# STM32F407ZGT6__2025-05-17.net
KiCad netlist of a schematic drawn in Altium Designer
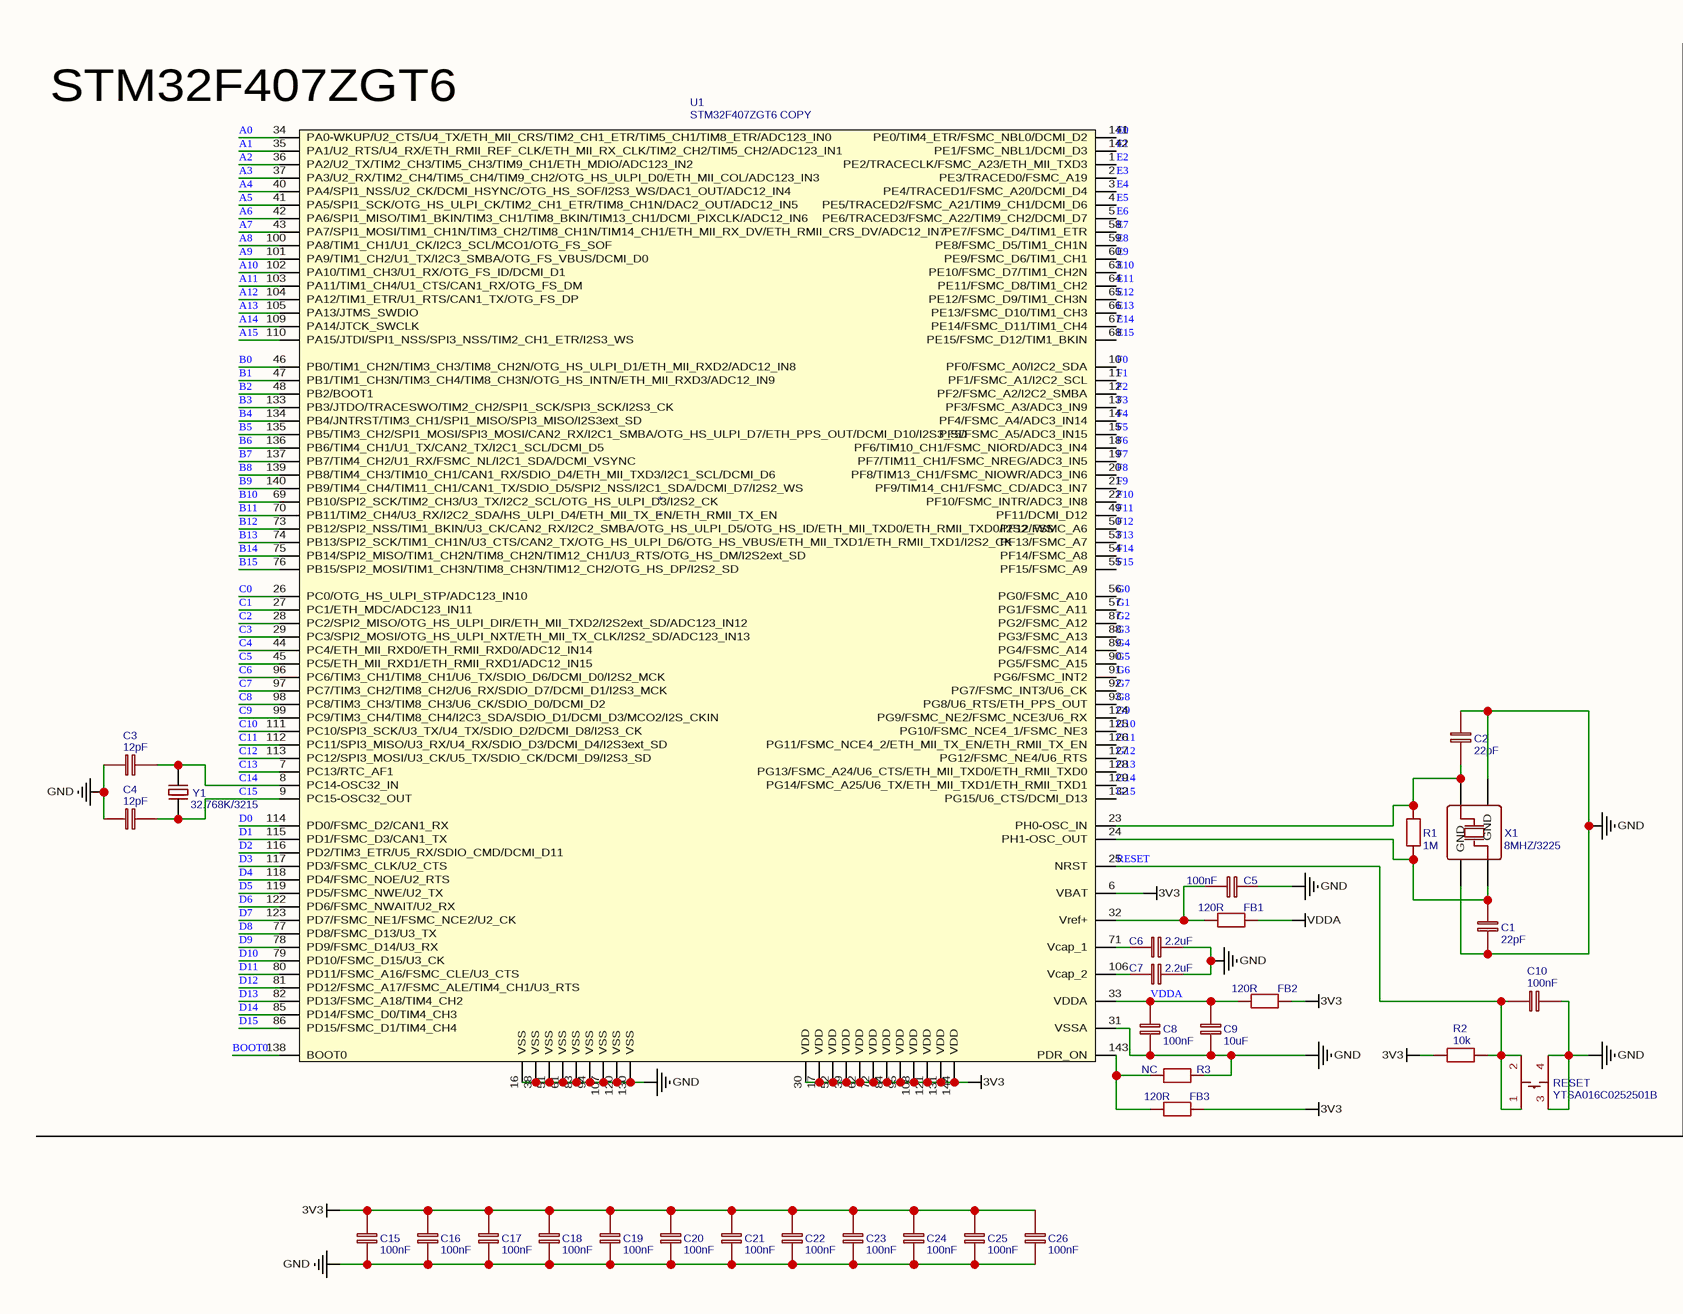
[diagram p0: STM32F407ZGT6最小系统原理图_2025-05-17.schdoc, left]
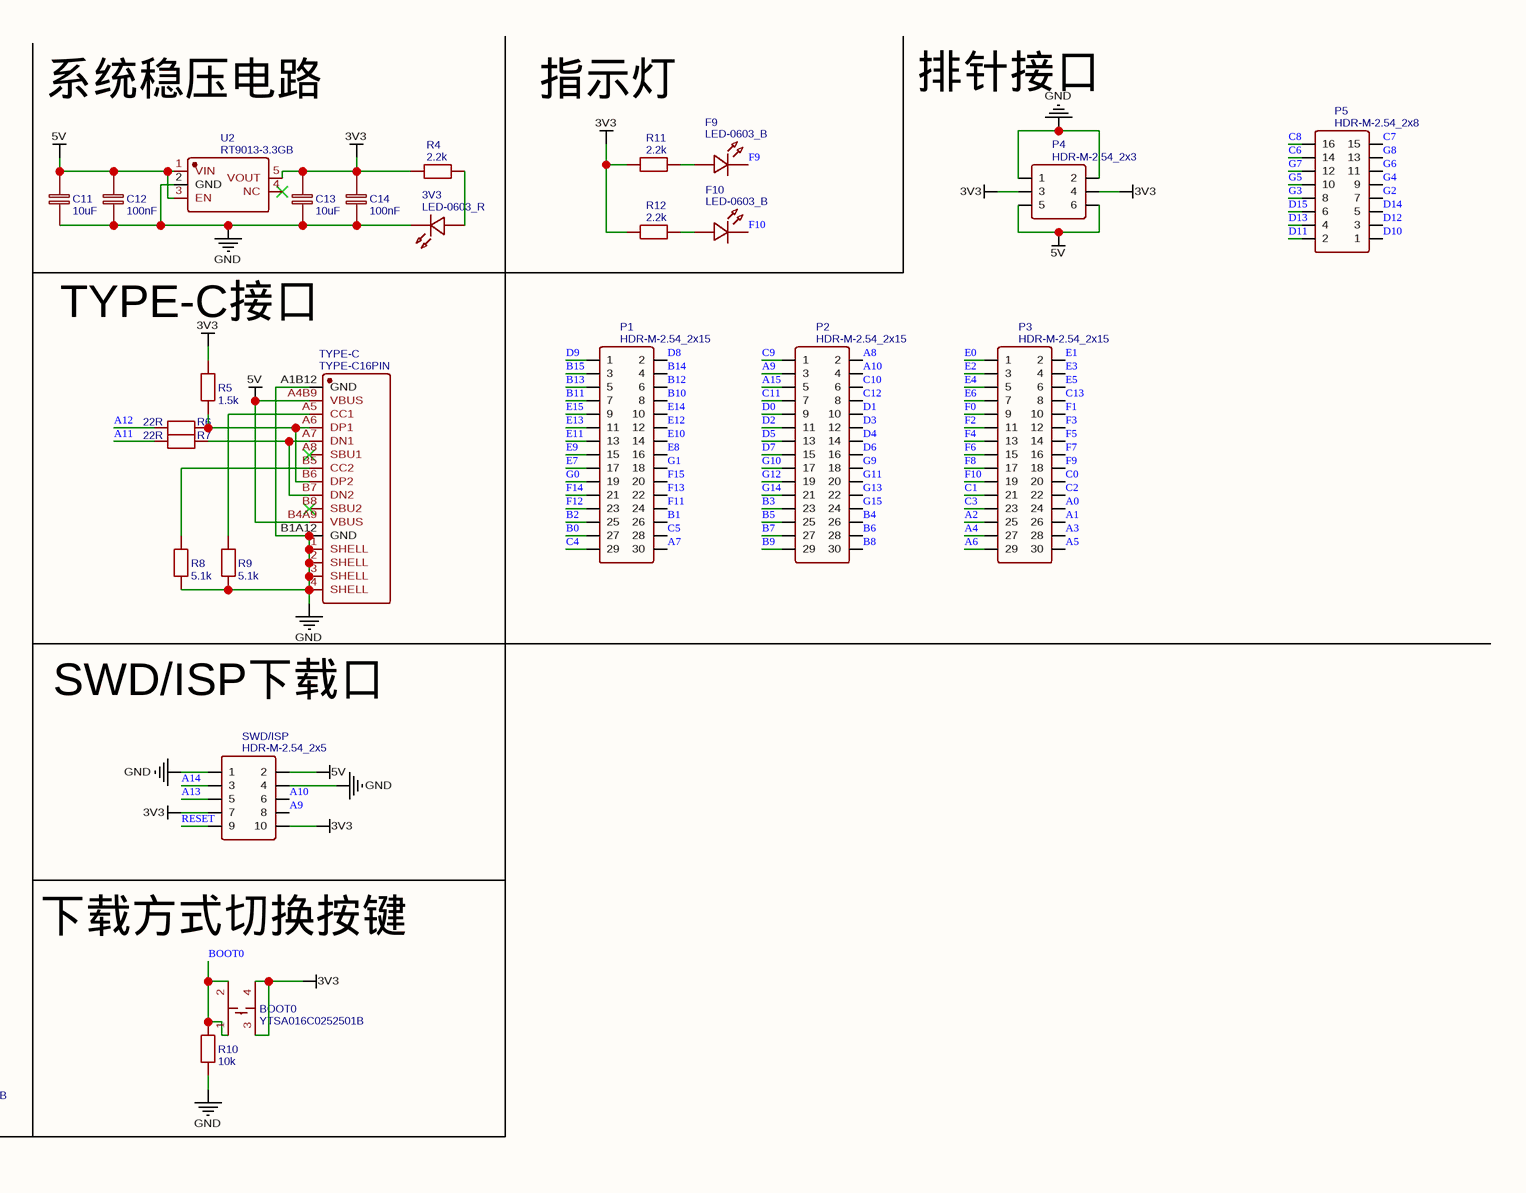
[diagram p1: STM32F407ZGT6最小系统原理图_2025-05-17.schdoc, right]

(export (version "E")
  (design (tool "Eeschema 10.0.6"))
  (components
    (comp (ref "3V3")
      (value "LED-0603_R")
      (fields
        (field (name "MANUFACTURER") "EVERLIGHT(台湾亿光)")
        (field (name "MANUFACTURER PART") "19-217/R6C-AL1M2VY/3T")
      )
      (libsource (lib "altium-import") (part "root_2_LED-0603_R_"))
    )
    (comp (ref "BOOT0")
      (value "YTSA016C0252501B")
      (fields (field (name "MANUFACTURER") "DGBZ"))
      (libsource (lib "altium-import") (part "root_1_YTSA016C0252501B_"))
    )
    (comp (ref "C1") (value "22pF") (libsource (lib "altium-import") (part "root_3_22pF_")))
    (comp (ref "C2") (value "22pF") (libsource (lib "altium-import") (part "root_3_22pF_")))
    (comp (ref "C3") (value "12pF") (libsource (lib "altium-import") (part "root_0_12pF_")))
    (comp (ref "C4") (value "12pF") (libsource (lib "altium-import") (part "root_0_12pF_")))
    (comp (ref "C5") (value "100nF") (libsource (lib "altium-import") (part "root_2_100nF_")))
    (comp (ref "C6") (value "2.2uF") (libsource (lib "altium-import") (part "root_0_2.2uF_")))
    (comp (ref "C7") (value "2.2uF") (libsource (lib "altium-import") (part "root_0_2.2uF_")))
    (comp (ref "C8") (value "100nF") (libsource (lib "altium-import") (part "root_1_100nF_")))
    (comp (ref "C9") (value "10uF") (libsource (lib "altium-import") (part "root_1_10uF_")))
    (comp (ref "C10") (value "100nF") (libsource (lib "altium-import") (part "root_0_100nF_")))
    (comp (ref "C11") (value "10uF") (libsource (lib "altium-import") (part "root_1_10uF_")))
    (comp (ref "C12") (value "100nF") (libsource (lib "altium-import") (part "root_1_100nF_")))
    (comp (ref "C13") (value "10uF") (libsource (lib "altium-import") (part "root_1_10uF_")))
    (comp (ref "C14") (value "100nF") (libsource (lib "altium-import") (part "root_1_100nF_")))
    (comp (ref "C15") (value "100nF") (libsource (lib "altium-import") (part "root_1_100nF_")))
    (comp (ref "C16") (value "100nF") (libsource (lib "altium-import") (part "root_1_100nF_")))
    (comp (ref "C17") (value "100nF") (libsource (lib "altium-import") (part "root_1_100nF_")))
    (comp (ref "C18") (value "100nF") (libsource (lib "altium-import") (part "root_1_100nF_")))
    (comp (ref "C19") (value "100nF") (libsource (lib "altium-import") (part "root_1_100nF_")))
    (comp (ref "C20") (value "100nF") (libsource (lib "altium-import") (part "root_1_100nF_")))
    (comp (ref "C21") (value "100nF") (libsource (lib "altium-import") (part "root_1_100nF_")))
    (comp (ref "C22") (value "100nF") (libsource (lib "altium-import") (part "root_1_100nF_")))
    (comp (ref "C23") (value "100nF") (libsource (lib "altium-import") (part "root_1_100nF_")))
    (comp (ref "C24") (value "100nF") (libsource (lib "altium-import") (part "root_1_100nF_")))
    (comp (ref "C25") (value "100nF") (libsource (lib "altium-import") (part "root_1_100nF_")))
    (comp (ref "C26") (value "100nF") (libsource (lib "altium-import") (part "root_1_100nF_")))
    (comp (ref "F9")
      (value "LED-0603_B")
      (fields
        (field (name "MANUFACTURER") "EVERLIGHT(台湾亿光)")
        (field (name "MANUFACTURER PART") "19-217/BHC-ZL1M2RY/3T")
      )
      (libsource (lib "altium-import") (part "root_0_LED-0603_B_"))
    )
    (comp (ref "F10")
      (value "LED-0603_B")
      (fields
        (field (name "MANUFACTURER") "EVERLIGHT(台湾亿光)")
        (field (name "MANUFACTURER PART") "19-217/BHC-ZL1M2RY/3T")
      )
      (libsource (lib "altium-import") (part "root_0_LED-0603_B_"))
    )
    (comp (ref "FB1") (value "120R") (libsource (lib "altium-import") (part "root_0_120R_")))
    (comp (ref "FB2") (value "120R") (libsource (lib "altium-import") (part "root_0_120R_")))
    (comp (ref "FB3") (value "120R") (libsource (lib "altium-import") (part "root_0_120R_")))
    (comp (ref "P1")
      (value "HDR-M-2.54_2x15")
      (libsource (lib "altium-import") (part "root_0_HDR-M-2.54_2x15_"))
    )
    (comp (ref "P2")
      (value "HDR-M-2.54_2x15")
      (libsource (lib "altium-import") (part "root_0_HDR-M-2.54_2x15_"))
    )
    (comp (ref "P3")
      (value "HDR-M-2.54_2x15")
      (libsource (lib "altium-import") (part "root_0_HDR-M-2.54_2x15_"))
    )
    (comp (ref "P4")
      (value "HDR-M-2.54_2x3")
      (libsource (lib "altium-import") (part "root_0_HDR-M-2.54_2x3_"))
    )
    (comp (ref "P5")
      (value "HDR-M-2.54_2x8")
      (libsource (lib "altium-import") (part "root_2_HDR-M-2.54_2x8_"))
    )
    (comp (ref "R1") (value "1M") (libsource (lib "altium-import") (part "root_1_1M_")))
    (comp (ref "R2") (value "10k") (libsource (lib "altium-import") (part "root_0_10k_")))
    (comp (ref "R3") (value "NC") (libsource (lib "altium-import") (part "root_0_NC_")))
    (comp (ref "R4") (value "2.2k") (libsource (lib "altium-import") (part "root_2_2.2k_")))
    (comp (ref "R5") (value "1.5k") (libsource (lib "altium-import") (part "root_1_1.5k_")))
    (comp (ref "R6") (value "22R") (libsource (lib "altium-import") (part "root_0_22R_")))
    (comp (ref "R7") (value "22R") (libsource (lib "altium-import") (part "root_0_22R_")))
    (comp (ref "R8") (value "5.1k") (libsource (lib "altium-import") (part "root_1_5.1k_")))
    (comp (ref "R9") (value "5.1k") (libsource (lib "altium-import") (part "root_1_5.1k_")))
    (comp (ref "R10") (value "10k") (libsource (lib "altium-import") (part "root_1_10k_")))
    (comp (ref "R11") (value "2.2k") (libsource (lib "altium-import") (part "root_0_2.2k_")))
    (comp (ref "R12") (value "2.2k") (libsource (lib "altium-import") (part "root_0_2.2k_")))
    (comp (ref "RESET")
      (value "YTSA016C0252501B")
      (fields (field (name "MANUFACTURER") "DGBZ"))
      (libsource (lib "altium-import") (part "root_1_YTSA016C0252501B_"))
    )
    (comp (ref "SWD/ISP")
      (value "HDR-M-2.54_2x5")
      (libsource (lib "altium-import") (part "root_0_HDR-M-2.54_2x5_"))
    )
    (comp (ref "TYPE-C")
      (value "TYPE-C16PIN")
      (fields (field (name "MANUFACTURER") "SHOU HAN"))
      (libsource (lib "altium-import") (part "root_0_TYPE-C16PIN_"))
    )
    (comp (ref "U1")
      (value "STM32F407ZGT6 COPY")
      (libsource (lib "altium-import") (part "root_0_STM32F407ZGT6 COPY_"))
    )
    (comp (ref "U2") (value "RT9013-3.3GB") (libsource (lib "altium-import") (part "root_0_RT9013-3.3GB_")))
    (comp (ref "X1")
      (value "8MHZ/3225")
      (fields (field (name "MANUFACTURER PART") "8Mhz/20PF/10PPM/40R内阻/无源晶振3225"))
      (libsource (lib "altium-import") (part "root_1_8MHZ/3225_"))
    )
    (comp (ref "Y1")
      (value "32.768K/3215")
      (fields (field (name "MANUFACTURER PART") "32.768K-OSC3215-2P"))
      (libsource (lib "altium-import") (part "root_1_32.768K/3215_"))
    )
  )
  (nets
    (net (code "1") (name "/A0") (class "Default")
      (node (ref "P3") (pin "24") (pinfunction "24_24") (pintype "passive"))
      (node (ref "U1") (pin "34") (pinfunction "PA0-WKUP/U2_CTS/U4_TX/ETH_MII_CRS/TIM2_CH1_ETR/TIM5_CH1/TIM8_ETR/ADC123_IN0_34") (pintype "passive"))
    )
    (net (code "2") (name "/A1") (class "Default")
      (node (ref "P3") (pin "26") (pinfunction "26_26") (pintype "passive"))
      (node (ref "U1") (pin "35") (pinfunction "PA1/U2_RTS/U4_RX/ETH_RMII_REF_CLK/ETH_MII_RX_CLK/TIM2_CH2/TIM5_CH2/ADC123_IN1_35") (pintype "passive"))
    )
    (net (code "3") (name "/A2") (class "Default")
      (node (ref "P3") (pin "25") (pinfunction "25_25") (pintype "passive"))
      (node (ref "U1") (pin "36") (pinfunction "PA2/U2_TX/TIM2_CH3/TIM5_CH3/TIM9_CH1/ETH_MDIO/ADC123_IN2_36") (pintype "passive"))
    )
    (net (code "4") (name "/A3") (class "Default")
      (node (ref "P3") (pin "28") (pinfunction "28_28") (pintype "passive"))
      (node (ref "U1") (pin "37") (pinfunction "PA3/U2_RX/TIM2_CH4/TIM5_CH4/TIM9_CH2/OTG_HS_ULPI_D0/ETH_MII_COL/ADC123_IN3_37") (pintype "passive"))
    )
    (net (code "5") (name "/A4") (class "Default")
      (node (ref "P3") (pin "27") (pinfunction "27_27") (pintype "passive"))
      (node (ref "U1") (pin "40") (pinfunction "PA4/SPI1_NSS/U2_CK/DCMI_HSYNC/OTG_HS_SOF/I2S3_WS/DAC1_OUT/ADC12_IN4_40") (pintype "passive"))
    )
    (net (code "6") (name "/A5") (class "Default")
      (node (ref "P3") (pin "30") (pinfunction "30_30") (pintype "passive"))
      (node (ref "U1") (pin "41") (pinfunction "PA5/SPI1_SCK/OTG_HS_ULPI_CK/TIM2_CH1_ETR/TIM8_CH1N/DAC2_OUT/ADC12_IN5_41") (pintype "passive"))
    )
    (net (code "7") (name "/A6") (class "Default")
      (node (ref "P3") (pin "29") (pinfunction "29_29") (pintype "passive"))
      (node (ref "U1") (pin "42") (pinfunction "PA6/SPI1_MISO/TIM1_BKIN/TIM3_CH1/TIM8_BKIN/TIM13_CH1/DCMI_PIXCLK/ADC12_IN6_42") (pintype "passive"))
    )
    (net (code "8") (name "/A7") (class "Default")
      (node (ref "P1") (pin "30") (pinfunction "30_30") (pintype "passive"))
      (node (ref "U1") (pin "43") (pinfunction "PA7/SPI1_MOSI/TIM1_CH1N/TIM3_CH2/TIM8_CH1N/TIM14_CH1/ETH_MII_RX_DV/ETH_RMII_CRS_DV/ADC12_IN7_43") (pintype "passive"))
    )
    (net (code "9") (name "/A8") (class "Default")
      (node (ref "P2") (pin "2") (pinfunction "2_2") (pintype "passive"))
      (node (ref "U1") (pin "100") (pinfunction "PA8/TIM1_CH1/U1_CK/I2C3_SCL/MCO1/OTG_FS_SOF_100") (pintype "passive"))
    )
    (net (code "10") (name "/A9") (class "Default")
      (node (ref "P2") (pin "3") (pinfunction "3_3") (pintype "passive"))
      (node (ref "SWD/ISP") (pin "8") (pinfunction "8_8") (pintype "passive"))
      (node (ref "U1") (pin "101") (pinfunction "PA9/TIM1_CH2/U1_TX/I2C3_SMBA/OTG_FS_VBUS/DCMI_D0_101") (pintype "passive"))
    )
    (net (code "11") (name "/A10") (class "Default")
      (node (ref "P2") (pin "4") (pinfunction "4_4") (pintype "passive"))
      (node (ref "SWD/ISP") (pin "6") (pinfunction "6_6") (pintype "passive"))
      (node (ref "U1") (pin "102") (pinfunction "PA10/TIM1_CH3/U1_RX/OTG_FS_ID/DCMI_D1_102") (pintype "passive"))
    )
    (net (code "12") (name "/A11") (class "Default")
      (node (ref "R7") (pin "1") (pinfunction "1_1") (pintype "passive"))
      (node (ref "U1") (pin "103") (pinfunction "PA11/TIM1_CH4/U1_CTS/CAN1_RX/OTG_FS_DM_103") (pintype "passive"))
    )
    (net (code "13") (name "/A12") (class "Default")
      (node (ref "R6") (pin "1") (pinfunction "1_1") (pintype "passive"))
      (node (ref "U1") (pin "104") (pinfunction "PA12/TIM1_ETR/U1_RTS/CAN1_TX/OTG_FS_DP_104") (pintype "passive"))
    )
    (net (code "14") (name "/A13") (class "Default")
      (node (ref "SWD/ISP") (pin "5") (pinfunction "5_5") (pintype "passive"))
      (node (ref "U1") (pin "105") (pinfunction "PA13/JTMS_SWDIO_105") (pintype "passive"))
    )
    (net (code "15") (name "/A14") (class "Default")
      (node (ref "SWD/ISP") (pin "3") (pinfunction "3_3") (pintype "passive"))
      (node (ref "U1") (pin "109") (pinfunction "PA14/JTCK_SWCLK_109") (pintype "passive"))
    )
    (net (code "16") (name "/A15") (class "Default")
      (node (ref "P2") (pin "5") (pinfunction "5_5") (pintype "passive"))
      (node (ref "U1") (pin "110") (pinfunction "PA15/JTDI/SPI1_NSS/SPI3_NSS/TIM2_CH1_ETR/I2S3_WS_110") (pintype "passive"))
    )
    (net (code "17") (name "/B0") (class "Default")
      (node (ref "P1") (pin "27") (pinfunction "27_27") (pintype "passive"))
      (node (ref "U1") (pin "46") (pinfunction "PB0/TIM1_CH2N/TIM3_CH3/TIM8_CH2N/OTG_HS_ULPI_D1/ETH_MII_RXD2/ADC12_IN8_46") (pintype "passive"))
    )
    (net (code "18") (name "/B1") (class "Default")
      (node (ref "P1") (pin "26") (pinfunction "26_26") (pintype "passive"))
      (node (ref "U1") (pin "47") (pinfunction "PB1/TIM1_CH3N/TIM3_CH4/TIM8_CH3N/OTG_HS_INTN/ETH_MII_RXD3/ADC12_IN9_47") (pintype "passive"))
    )
    (net (code "19") (name "/B2") (class "Default")
      (node (ref "P1") (pin "25") (pinfunction "25_25") (pintype "passive"))
      (node (ref "U1") (pin "48") (pinfunction "PB2/BOOT1_48") (pintype "passive"))
    )
    (net (code "20") (name "/B3") (class "Default")
      (node (ref "P2") (pin "23") (pinfunction "23_23") (pintype "passive"))
      (node (ref "U1") (pin "133") (pinfunction "PB3/JTDO/TRACESWO/TIM2_CH2/SPI1_SCK/SPI3_SCK/I2S3_CK_133") (pintype "passive"))
    )
    (net (code "21") (name "/B4") (class "Default")
      (node (ref "P2") (pin "26") (pinfunction "26_26") (pintype "passive"))
      (node (ref "U1") (pin "134") (pinfunction "PB4/JNTRST/TIM3_CH1/SPI1_MISO/SPI3_MISO/I2S3ext_SD_134") (pintype "passive"))
    )
    (net (code "22") (name "/B5") (class "Default")
      (node (ref "P2") (pin "25") (pinfunction "25_25") (pintype "passive"))
      (node (ref "U1") (pin "135") (pinfunction "PB5/TIM3_CH2/SPI1_MOSI/SPI3_MOSI/CAN2_RX/I2C1_SMBA/OTG_HS_ULPI_D7/ETH_PPS_OUT/DCMI_D10/I2S3_SD_135") (pintype "passive"))
    )
    (net (code "23") (name "/B6") (class "Default")
      (node (ref "P2") (pin "28") (pinfunction "28_28") (pintype "passive"))
      (node (ref "U1") (pin "136") (pinfunction "PB6/TIM4_CH1/U1_TX/CAN2_TX/I2C1_SCL/DCMI_D5_136") (pintype "passive"))
    )
    (net (code "24") (name "/B7") (class "Default")
      (node (ref "P2") (pin "27") (pinfunction "27_27") (pintype "passive"))
      (node (ref "U1") (pin "137") (pinfunction "PB7/TIM4_CH2/U1_RX/FSMC_NL/I2C1_SDA/DCMI_VSYNC_137") (pintype "passive"))
    )
    (net (code "25") (name "/B8") (class "Default")
      (node (ref "P2") (pin "30") (pinfunction "30_30") (pintype "passive"))
      (node (ref "U1") (pin "139") (pinfunction "PB8/TIM4_CH3/TIM10_CH1/CAN1_RX/SDIO_D4/ETH_MII_TXD3/I2C1_SCL/DCMI_D6_139") (pintype "passive"))
    )
    (net (code "26") (name "/B9") (class "Default")
      (node (ref "P2") (pin "29") (pinfunction "29_29") (pintype "passive"))
      (node (ref "U1") (pin "140") (pinfunction "PB9/TIM4_CH4/TIM11_CH1/CAN1_TX/SDIO_D5/SPI2_NSS/I2C1_SDA/DCMI_D7/I2S2_WS_140") (pintype "passive"))
    )
    (net (code "27") (name "/B10") (class "Default")
      (node (ref "P1") (pin "8") (pinfunction "8_8") (pintype "passive"))
      (node (ref "U1") (pin "69") (pinfunction "PB10/SPI2_SCK/TIM2_CH3/U3_TX/I2C2_SCL/OTG_HS_ULPI_D3/I2S2_CK_69") (pintype "passive"))
    )
    (net (code "28") (name "/B11") (class "Default")
      (node (ref "P1") (pin "7") (pinfunction "7_7") (pintype "passive"))
      (node (ref "U1") (pin "70") (pinfunction "PB11/TIM2_CH4/U3_RX/I2C2_SDA/HS_ULPI_D4/ETH_MII_TX_EN/ETH_RMII_TX_EN_70") (pintype "passive"))
    )
    (net (code "29") (name "/B12") (class "Default")
      (node (ref "P1") (pin "6") (pinfunction "6_6") (pintype "passive"))
      (node (ref "U1") (pin "73") (pinfunction "PB12/SPI2_NSS/TIM1_BKIN/U3_CK/CAN2_RX/I2C2_SMBA/OTG_HS_ULPI_D5/OTG_HS_ID/ETH_MII_TXD0/ETH_RMII_TXD0/I2S2_WS_73") (pintype "passive"))
    )
    (net (code "30") (name "/B13") (class "Default")
      (node (ref "P1") (pin "5") (pinfunction "5_5") (pintype "passive"))
      (node (ref "U1") (pin "74") (pinfunction "PB13/SPI2_SCK/TIM1_CH1N/U3_CTS/CAN2_TX/OTG_HS_ULPI_D6/OTG_HS_VBUS/ETH_MII_TXD1/ETH_RMII_TXD1/I2S2_CK_74") (pintype "passive"))
    )
    (net (code "31") (name "/B14") (class "Default")
      (node (ref "P1") (pin "4") (pinfunction "4_4") (pintype "passive"))
      (node (ref "U1") (pin "75") (pinfunction "PB14/SPI2_MISO/TIM1_CH2N/TIM8_CH2N/TIM12_CH1/U3_RTS/OTG_HS_DM/I2S2ext_SD_75") (pintype "passive"))
    )
    (net (code "32") (name "/B15") (class "Default")
      (node (ref "P1") (pin "3") (pinfunction "3_3") (pintype "passive"))
      (node (ref "U1") (pin "76") (pinfunction "PB15/SPI2_MOSI/TIM1_CH3N/TIM8_CH3N/TIM12_CH2/OTG_HS_DP/I2S2_SD_76") (pintype "passive"))
    )
    (net (code "33") (name "/BOOT0") (class "Default")
      (node (ref "BOOT0") (pin "1") (pinfunction "1_1") (pintype "passive"))
      (node (ref "BOOT0") (pin "2") (pinfunction "2_2") (pintype "passive"))
      (node (ref "R10") (pin "2") (pinfunction "2_2") (pintype "passive"))
      (node (ref "U1") (pin "138") (pinfunction "BOOT0_138") (pintype "passive"))
    )
    (net (code "34") (name "/C0") (class "Default")
      (node (ref "P3") (pin "20") (pinfunction "20_20") (pintype "passive"))
      (node (ref "U1") (pin "26") (pinfunction "PC0/OTG_HS_ULPI_STP/ADC123_IN10_26") (pintype "passive"))
    )
    (net (code "35") (name "/C1") (class "Default")
      (node (ref "P3") (pin "21") (pinfunction "21_21") (pintype "passive"))
      (node (ref "U1") (pin "27") (pinfunction "PC1/ETH_MDC/ADC123_IN11_27") (pintype "passive"))
    )
    (net (code "36") (name "/C2") (class "Default")
      (node (ref "P3") (pin "22") (pinfunction "22_22") (pintype "passive"))
      (node (ref "U1") (pin "28") (pinfunction "PC2/SPI2_MISO/OTG_HS_ULPI_DIR/ETH_MII_TXD2/I2S2ext_SD/ADC123_IN12_28") (pintype "passive"))
    )
    (net (code "37") (name "/C3") (class "Default")
      (node (ref "P3") (pin "23") (pinfunction "23_23") (pintype "passive"))
      (node (ref "U1") (pin "29") (pinfunction "PC3/SPI2_MOSI/OTG_HS_ULPI_NXT/ETH_MII_TX_CLK/I2S2_SD/ADC123_IN13_29") (pintype "passive"))
    )
    (net (code "38") (name "/C4") (class "Default")
      (node (ref "P1") (pin "29") (pinfunction "29_29") (pintype "passive"))
      (node (ref "U1") (pin "44") (pinfunction "PC4/ETH_MII_RXD0/ETH_RMII_RXD0/ADC12_IN14_44") (pintype "passive"))
    )
    (net (code "39") (name "/C5") (class "Default")
      (node (ref "P1") (pin "28") (pinfunction "28_28") (pintype "passive"))
      (node (ref "U1") (pin "45") (pinfunction "PC5/ETH_MII_RXD1/ETH_RMII_RXD1/ADC12_IN15_45") (pintype "passive"))
    )
    (net (code "40") (name "/C6") (class "Default")
      (node (ref "P5") (pin "14") (pinfunction "14_14") (pintype "passive"))
      (node (ref "U1") (pin "96") (pinfunction "PC6/TIM3_CH1/TIM8_CH1/U6_TX/SDIO_D6/DCMI_D0/I2S2_MCK_96") (pintype "passive"))
    )
    (net (code "41") (name "/C7") (class "Default")
      (node (ref "P5") (pin "15") (pinfunction "15_15") (pintype "passive"))
      (node (ref "U1") (pin "97") (pinfunction "PC7/TIM3_CH2/TIM8_CH2/U6_RX/SDIO_D7/DCMI_D1/I2S3_MCK_97") (pintype "passive"))
    )
    (net (code "42") (name "/C8") (class "Default")
      (node (ref "P5") (pin "16") (pinfunction "16_16") (pintype "passive"))
      (node (ref "U1") (pin "98") (pinfunction "PC8/TIM3_CH3/TIM8_CH3/U6_CK/SDIO_D0/DCMI_D2_98") (pintype "passive"))
    )
    (net (code "43") (name "/C9") (class "Default")
      (node (ref "P2") (pin "1") (pinfunction "1_1") (pintype "passive"))
      (node (ref "U1") (pin "99") (pinfunction "PC9/TIM3_CH4/TIM8_CH4/I2C3_SDA/SDIO_D1/DCMI_D3/MCO2/I2S_CKIN_99") (pintype "passive"))
    )
    (net (code "44") (name "/C10") (class "Default")
      (node (ref "P2") (pin "6") (pinfunction "6_6") (pintype "passive"))
      (node (ref "U1") (pin "111") (pinfunction "PC10/SPI3_SCK/U3_TX/U4_TX/SDIO_D2/DCMI_D8/I2S3_CK_111") (pintype "passive"))
    )
    (net (code "45") (name "/C11") (class "Default")
      (node (ref "P2") (pin "7") (pinfunction "7_7") (pintype "passive"))
      (node (ref "U1") (pin "112") (pinfunction "PC11/SPI3_MISO/U3_RX/U4_RX/SDIO_D3/DCMI_D4/I2S3ext_SD_112") (pintype "passive"))
    )
    (net (code "46") (name "/C12") (class "Default")
      (node (ref "P2") (pin "8") (pinfunction "8_8") (pintype "passive"))
      (node (ref "U1") (pin "113") (pinfunction "PC12/SPI3_MOSI/U3_CK/U5_TX/SDIO_CK/DCMI_D9/I2S3_SD_113") (pintype "passive"))
    )
    (net (code "47") (name "/C13") (class "Default")
      (node (ref "P3") (pin "8") (pinfunction "8_8") (pintype "passive"))
      (node (ref "U1") (pin "7") (pinfunction "PC13/RTC_AF1_7") (pintype "passive"))
    )
    (net (code "48") (name "/C14") (class "Default")
      (node (ref "C3") (pin "2") (pinfunction "2_2") (pintype "passive"))
      (node (ref "U1") (pin "8") (pinfunction "PC14-OSC32_IN_8") (pintype "passive"))
      (node (ref "Y1") (pin "2") (pinfunction "GND_2") (pintype "passive"))
    )
    (net (code "49") (name "/C15") (class "Default")
      (node (ref "C4") (pin "2") (pinfunction "2_2") (pintype "passive"))
      (node (ref "U1") (pin "9") (pinfunction "PC15-OSC32_OUT_9") (pintype "passive"))
      (node (ref "Y1") (pin "1") (pinfunction "1_1") (pintype "passive"))
    )
    (net (code "50") (name "/D0") (class "Default")
      (node (ref "P2") (pin "9") (pinfunction "9_9") (pintype "passive"))
      (node (ref "U1") (pin "114") (pinfunction "PD0/FSMC_D2/CAN1_RX_114") (pintype "passive"))
    )
    (net (code "51") (name "/D1") (class "Default")
      (node (ref "P2") (pin "10") (pinfunction "10_10") (pintype "passive"))
      (node (ref "U1") (pin "115") (pinfunction "PD1/FSMC_D3/CAN1_TX_115") (pintype "passive"))
    )
    (net (code "52") (name "/D2") (class "Default")
      (node (ref "P2") (pin "11") (pinfunction "11_11") (pintype "passive"))
      (node (ref "U1") (pin "116") (pinfunction "PD2/TIM3_ETR/U5_RX/SDIO_CMD/DCMI_D11_116") (pintype "passive"))
    )
    (net (code "53") (name "/D3") (class "Default")
      (node (ref "P2") (pin "12") (pinfunction "12_12") (pintype "passive"))
      (node (ref "U1") (pin "117") (pinfunction "PD3/FSMC_CLK/U2_CTS_117") (pintype "passive"))
    )
    (net (code "54") (name "/D4") (class "Default")
      (node (ref "P2") (pin "14") (pinfunction "14_14") (pintype "passive"))
      (node (ref "U1") (pin "118") (pinfunction "PD4/FSMC_NOE/U2_RTS_118") (pintype "passive"))
    )
    (net (code "55") (name "/D5") (class "Default")
      (node (ref "P2") (pin "13") (pinfunction "13_13") (pintype "passive"))
      (node (ref "U1") (pin "119") (pinfunction "PD5/FSMC_NWE/U2_TX_119") (pintype "passive"))
    )
    (net (code "56") (name "/D6") (class "Default")
      (node (ref "P2") (pin "16") (pinfunction "16_16") (pintype "passive"))
      (node (ref "U1") (pin "122") (pinfunction "PD6/FSMC_NWAIT/U2_RX_122") (pintype "passive"))
    )
    (net (code "57") (name "/D7") (class "Default")
      (node (ref "P2") (pin "15") (pinfunction "15_15") (pintype "passive"))
      (node (ref "U1") (pin "123") (pinfunction "PD7/FSMC_NE1/FSMC_NCE2/U2_CK_123") (pintype "passive"))
    )
    (net (code "58") (name "/D8") (class "Default")
      (node (ref "P1") (pin "2") (pinfunction "2_2") (pintype "passive"))
      (node (ref "U1") (pin "77") (pinfunction "PD8/FSMC_D13/U3_TX_77") (pintype "passive"))
    )
    (net (code "59") (name "/D9") (class "Default")
      (node (ref "P1") (pin "1") (pinfunction "1_1") (pintype "passive"))
      (node (ref "U1") (pin "78") (pinfunction "PD9/FSMC_D14/U3_RX_78") (pintype "passive"))
    )
    (net (code "60") (name "/D10") (class "Default")
      (node (ref "P5") (pin "1") (pinfunction "1_1") (pintype "passive"))
      (node (ref "U1") (pin "79") (pinfunction "PD10/FSMC_D15/U3_CK_79") (pintype "passive"))
    )
    (net (code "61") (name "/D11") (class "Default")
      (node (ref "P5") (pin "2") (pinfunction "2_2") (pintype "passive"))
      (node (ref "U1") (pin "80") (pinfunction "PD11/FSMC_A16/FSMC_CLE/U3_CTS_80") (pintype "passive"))
    )
    (net (code "62") (name "/D12") (class "Default")
      (node (ref "P5") (pin "3") (pinfunction "3_3") (pintype "passive"))
      (node (ref "U1") (pin "81") (pinfunction "PD12/FSMC_A17/FSMC_ALE/TIM4_CH1/U3_RTS_81") (pintype "passive"))
    )
    (net (code "63") (name "/D13") (class "Default")
      (node (ref "P5") (pin "4") (pinfunction "4_4") (pintype "passive"))
      (node (ref "U1") (pin "82") (pinfunction "PD13/FSMC_A18/TIM4_CH2_82") (pintype "passive"))
    )
    (net (code "64") (name "/D14") (class "Default")
      (node (ref "P5") (pin "5") (pinfunction "5_5") (pintype "passive"))
      (node (ref "U1") (pin "85") (pinfunction "PD14/FSMC_D0/TIM4_CH3_85") (pintype "passive"))
    )
    (net (code "65") (name "/D15") (class "Default")
      (node (ref "P5") (pin "6") (pinfunction "6_6") (pintype "passive"))
      (node (ref "U1") (pin "86") (pinfunction "PD15/FSMC_D1/TIM4_CH4_86") (pintype "passive"))
    )
    (net (code "66") (name "/E0") (class "Default")
      (node (ref "P3") (pin "1") (pinfunction "1_1") (pintype "passive"))
      (node (ref "U1") (pin "141") (pinfunction "PE0/TIM4_ETR/FSMC_NBL0/DCMI_D2_141") (pintype "passive"))
    )
    (net (code "67") (name "/E1") (class "Default")
      (node (ref "P3") (pin "2") (pinfunction "2_2") (pintype "passive"))
      (node (ref "U1") (pin "142") (pinfunction "PE1/FSMC_NBL1/DCMI_D3_142") (pintype "passive"))
    )
    (net (code "68") (name "/E2") (class "Default")
      (node (ref "P3") (pin "3") (pinfunction "3_3") (pintype "passive"))
      (node (ref "U1") (pin "1") (pinfunction "PE2/TRACECLK/FSMC_A23/ETH_MII_TXD3_1") (pintype "passive"))
    )
    (net (code "69") (name "/E3") (class "Default")
      (node (ref "P3") (pin "4") (pinfunction "4_4") (pintype "passive"))
      (node (ref "U1") (pin "2") (pinfunction "PE3/TRACED0/FSMC_A19_2") (pintype "passive"))
    )
    (net (code "70") (name "/E4") (class "Default")
      (node (ref "P3") (pin "5") (pinfunction "5_5") (pintype "passive"))
      (node (ref "U1") (pin "3") (pinfunction "PE4/TRACED1/FSMC_A20/DCMI_D4_3") (pintype "passive"))
    )
    (net (code "71") (name "/E5") (class "Default")
      (node (ref "P3") (pin "6") (pinfunction "6_6") (pintype "passive"))
      (node (ref "U1") (pin "4") (pinfunction "PE5/TRACED2/FSMC_A21/TIM9_CH1/DCMI_D6_4") (pintype "passive"))
    )
    (net (code "72") (name "/E6") (class "Default")
      (node (ref "P3") (pin "7") (pinfunction "7_7") (pintype "passive"))
      (node (ref "U1") (pin "5") (pinfunction "PE6/TRACED3/FSMC_A22/TIM9_CH2/DCMI_D7_5") (pintype "passive"))
    )
    (net (code "73") (name "/E7") (class "Default")
      (node (ref "P1") (pin "17") (pinfunction "17_17") (pintype "passive"))
      (node (ref "U1") (pin "58") (pinfunction "PE7/FSMC_D4/TIM1_ETR_58") (pintype "passive"))
    )
    (net (code "74") (name "/E8") (class "Default")
      (node (ref "P1") (pin "16") (pinfunction "16_16") (pintype "passive"))
      (node (ref "U1") (pin "59") (pinfunction "PE8/FSMC_D5/TIM1_CH1N_59") (pintype "passive"))
    )
    (net (code "75") (name "/E9") (class "Default")
      (node (ref "P1") (pin "15") (pinfunction "15_15") (pintype "passive"))
      (node (ref "U1") (pin "60") (pinfunction "PE9/FSMC_D6/TIM1_CH1_60") (pintype "passive"))
    )
    (net (code "76") (name "/E10") (class "Default")
      (node (ref "P1") (pin "14") (pinfunction "14_14") (pintype "passive"))
      (node (ref "U1") (pin "63") (pinfunction "PE10/FSMC_D7/TIM1_CH2N_63") (pintype "passive"))
    )
    (net (code "77") (name "/E11") (class "Default")
      (node (ref "P1") (pin "13") (pinfunction "13_13") (pintype "passive"))
      (node (ref "U1") (pin "64") (pinfunction "PE11/FSMC_D8/TIM1_CH2_64") (pintype "passive"))
    )
    (net (code "78") (name "/E12") (class "Default")
      (node (ref "P1") (pin "12") (pinfunction "12_12") (pintype "passive"))
      (node (ref "U1") (pin "65") (pinfunction "PE12/FSMC_D9/TIM1_CH3N_65") (pintype "passive"))
    )
    (net (code "79") (name "/E13") (class "Default")
      (node (ref "P1") (pin "11") (pinfunction "11_11") (pintype "passive"))
      (node (ref "U1") (pin "66") (pinfunction "PE13/FSMC_D10/TIM1_CH3_66") (pintype "passive"))
    )
    (net (code "80") (name "/E14") (class "Default")
      (node (ref "P1") (pin "10") (pinfunction "10_10") (pintype "passive"))
      (node (ref "U1") (pin "67") (pinfunction "PE14/FSMC_D11/TIM1_CH4_67") (pintype "passive"))
    )
    (net (code "81") (name "/E15") (class "Default")
      (node (ref "P1") (pin "9") (pinfunction "9_9") (pintype "passive"))
      (node (ref "U1") (pin "68") (pinfunction "PE15/FSMC_D12/TIM1_BKIN_68") (pintype "passive"))
    )
    (net (code "82") (name "/F0") (class "Default")
      (node (ref "P3") (pin "9") (pinfunction "9_9") (pintype "passive"))
      (node (ref "U1") (pin "10") (pinfunction "PF0/FSMC_A0/I2C2_SDA_10") (pintype "passive"))
    )
    (net (code "83") (name "/F1") (class "Default")
      (node (ref "P3") (pin "10") (pinfunction "10_10") (pintype "passive"))
      (node (ref "U1") (pin "11") (pinfunction "PF1/FSMC_A1/I2C2_SCL_11") (pintype "passive"))
    )
    (net (code "84") (name "/F2") (class "Default")
      (node (ref "P3") (pin "11") (pinfunction "11_11") (pintype "passive"))
      (node (ref "U1") (pin "12") (pinfunction "PF2/FSMC_A2/I2C2_SMBA_12") (pintype "passive"))
    )
    (net (code "85") (name "/F3") (class "Default")
      (node (ref "P3") (pin "12") (pinfunction "12_12") (pintype "passive"))
      (node (ref "U1") (pin "13") (pinfunction "PF3/FSMC_A3/ADC3_IN9_13") (pintype "passive"))
    )
    (net (code "86") (name "/F4") (class "Default")
      (node (ref "P3") (pin "13") (pinfunction "13_13") (pintype "passive"))
      (node (ref "U1") (pin "14") (pinfunction "PF4/FSMC_A4/ADC3_IN14_14") (pintype "passive"))
    )
    (net (code "87") (name "/F5") (class "Default")
      (node (ref "P3") (pin "14") (pinfunction "14_14") (pintype "passive"))
      (node (ref "U1") (pin "15") (pinfunction "PF5/FSMC_A5/ADC3_IN15_15") (pintype "passive"))
    )
    (net (code "88") (name "/F6") (class "Default")
      (node (ref "P3") (pin "15") (pinfunction "15_15") (pintype "passive"))
      (node (ref "U1") (pin "18") (pinfunction "PF6/TIM10_CH1/FSMC_NIORD/ADC3_IN4_18") (pintype "passive"))
    )
    (net (code "89") (name "/F7") (class "Default")
      (node (ref "P3") (pin "16") (pinfunction "16_16") (pintype "passive"))
      (node (ref "U1") (pin "19") (pinfunction "PF7/TIM11_CH1/FSMC_NREG/ADC3_IN5_19") (pintype "passive"))
    )
    (net (code "90") (name "/F8") (class "Default")
      (node (ref "P3") (pin "17") (pinfunction "17_17") (pintype "passive"))
      (node (ref "U1") (pin "20") (pinfunction "PF8/TIM13_CH1/FSMC_NIOWR/ADC3_IN6_20") (pintype "passive"))
    )
    (net (code "91") (name "/F9") (class "Default")
      (node (ref "F9") (pin "2") (pinfunction "2_2") (pintype "passive"))
      (node (ref "P3") (pin "18") (pinfunction "18_18") (pintype "passive"))
      (node (ref "U1") (pin "21") (pinfunction "PF9/TIM14_CH1/FSMC_CD/ADC3_IN7_21") (pintype "passive"))
    )
    (net (code "92") (name "/F10") (class "Default")
      (node (ref "F10") (pin "2") (pinfunction "2_2") (pintype "passive"))
      (node (ref "P3") (pin "19") (pinfunction "19_19") (pintype "passive"))
      (node (ref "U1") (pin "22") (pinfunction "PF10/FSMC_INTR/ADC3_IN8_22") (pintype "passive"))
    )
    (net (code "93") (name "/F11") (class "Default")
      (node (ref "P1") (pin "24") (pinfunction "24_24") (pintype "passive"))
      (node (ref "U1") (pin "49") (pinfunction "PF11/DCMI_D12_49") (pintype "passive"))
    )
    (net (code "94") (name "/F12") (class "Default")
      (node (ref "P1") (pin "23") (pinfunction "23_23") (pintype "passive"))
      (node (ref "U1") (pin "50") (pinfunction "PF12/FSMC_A6_50") (pintype "passive"))
    )
    (net (code "95") (name "/F13") (class "Default")
      (node (ref "P1") (pin "22") (pinfunction "22_22") (pintype "passive"))
      (node (ref "U1") (pin "53") (pinfunction "PF13/FSMC_A7_53") (pintype "passive"))
    )
    (net (code "96") (name "/F14") (class "Default")
      (node (ref "P1") (pin "21") (pinfunction "21_21") (pintype "passive"))
      (node (ref "U1") (pin "54") (pinfunction "PF14/FSMC_A8_54") (pintype "passive"))
    )
    (net (code "97") (name "/F15") (class "Default")
      (node (ref "P1") (pin "20") (pinfunction "20_20") (pintype "passive"))
      (node (ref "U1") (pin "55") (pinfunction "PF15/FSMC_A9_55") (pintype "passive"))
    )
    (net (code "98") (name "/G0") (class "Default")
      (node (ref "P1") (pin "19") (pinfunction "19_19") (pintype "passive"))
      (node (ref "U1") (pin "56") (pinfunction "PG0/FSMC_A10_56") (pintype "passive"))
    )
    (net (code "99") (name "/G1") (class "Default")
      (node (ref "P1") (pin "18") (pinfunction "18_18") (pintype "passive"))
      (node (ref "U1") (pin "57") (pinfunction "PG1/FSMC_A11_57") (pintype "passive"))
    )
    (net (code "100") (name "/G2") (class "Default")
      (node (ref "P5") (pin "7") (pinfunction "7_7") (pintype "passive"))
      (node (ref "U1") (pin "87") (pinfunction "PG2/FSMC_A12_87") (pintype "passive"))
    )
    (net (code "101") (name "/G3") (class "Default")
      (node (ref "P5") (pin "8") (pinfunction "8_8") (pintype "passive"))
      (node (ref "U1") (pin "88") (pinfunction "PG3/FSMC_A13_88") (pintype "passive"))
    )
    (net (code "102") (name "/G4") (class "Default")
      (node (ref "P5") (pin "9") (pinfunction "9_9") (pintype "passive"))
      (node (ref "U1") (pin "89") (pinfunction "PG4/FSMC_A14_89") (pintype "passive"))
    )
    (net (code "103") (name "/G5") (class "Default")
      (node (ref "P5") (pin "10") (pinfunction "10_10") (pintype "passive"))
      (node (ref "U1") (pin "90") (pinfunction "PG5/FSMC_A15_90") (pintype "passive"))
    )
    (net (code "104") (name "/G6") (class "Default")
      (node (ref "P5") (pin "11") (pinfunction "11_11") (pintype "passive"))
      (node (ref "U1") (pin "91") (pinfunction "PG6/FSMC_INT2_91") (pintype "passive"))
    )
    (net (code "105") (name "/G7") (class "Default")
      (node (ref "P5") (pin "12") (pinfunction "12_12") (pintype "passive"))
      (node (ref "U1") (pin "92") (pinfunction "PG7/FSMC_INT3/U6_CK_92") (pintype "passive"))
    )
    (net (code "106") (name "/G8") (class "Default")
      (node (ref "P5") (pin "13") (pinfunction "13_13") (pintype "passive"))
      (node (ref "U1") (pin "93") (pinfunction "PG8/U6_RTS/ETH_PPS_OUT_93") (pintype "passive"))
    )
    (net (code "107") (name "/G9") (class "Default")
      (node (ref "P2") (pin "18") (pinfunction "18_18") (pintype "passive"))
      (node (ref "U1") (pin "124") (pinfunction "PG9/FSMC_NE2/FSMC_NCE3/U6_RX_124") (pintype "passive"))
    )
    (net (code "108") (name "/G10") (class "Default")
      (node (ref "P2") (pin "17") (pinfunction "17_17") (pintype "passive"))
      (node (ref "U1") (pin "125") (pinfunction "PG10/FSMC_NCE4_1/FSMC_NE3_125") (pintype "passive"))
    )
    (net (code "109") (name "/G11") (class "Default")
      (node (ref "P2") (pin "20") (pinfunction "20_20") (pintype "passive"))
      (node (ref "U1") (pin "126") (pinfunction "PG11/FSMC_NCE4_2/ETH_MII_TX_EN/ETH_RMII_TX_EN_126") (pintype "passive"))
    )
    (net (code "110") (name "/G12") (class "Default")
      (node (ref "P2") (pin "19") (pinfunction "19_19") (pintype "passive"))
      (node (ref "U1") (pin "127") (pinfunction "PG12/FSMC_NE4/U6_RTS_127") (pintype "passive"))
    )
    (net (code "111") (name "/G13") (class "Default")
      (node (ref "P2") (pin "22") (pinfunction "22_22") (pintype "passive"))
      (node (ref "U1") (pin "128") (pinfunction "PG13/FSMC_A24/U6_CTS/ETH_MII_TXD0/ETH_RMII_TXD0_128") (pintype "passive"))
    )
    (net (code "112") (name "/G14") (class "Default")
      (node (ref "P2") (pin "21") (pinfunction "21_21") (pintype "passive"))
      (node (ref "U1") (pin "129") (pinfunction "PG14/FSMC_A25/U6_TX/ETH_MII_TXD1/ETH_RMII_TXD1_129") (pintype "passive"))
    )
    (net (code "113") (name "/G15") (class "Default")
      (node (ref "P2") (pin "24") (pinfunction "24_24") (pintype "passive"))
      (node (ref "U1") (pin "132") (pinfunction "PG15/U6_CTS/DCMI_D13_132") (pintype "passive"))
    )
    (net (code "114") (name "/RESET") (class "Default")
      (node (ref "C10") (pin "1") (pinfunction "1_1") (pintype "passive"))
      (node (ref "R2") (pin "2") (pinfunction "2_2") (pintype "passive"))
      (node (ref "RESET") (pin "1") (pinfunction "1_1") (pintype "passive"))
      (node (ref "RESET") (pin "2") (pinfunction "2_2") (pintype "passive"))
      (node (ref "SWD/ISP") (pin "9") (pinfunction "9_9") (pintype "passive"))
      (node (ref "U1") (pin "25") (pinfunction "NRST_25") (pintype "passive"))
    )
    (net (code "115") (name "3V3") (class "Default")
      (node (ref "BOOT0") (pin "3") (pinfunction "3_3") (pintype "passive"))
      (node (ref "BOOT0") (pin "4") (pinfunction "4_4") (pintype "passive"))
      (node (ref "C13") (pin "2") (pinfunction "2_2") (pintype "passive"))
      (node (ref "C14") (pin "2") (pinfunction "2_2") (pintype "passive"))
      (node (ref "C15") (pin "2") (pinfunction "2_2") (pintype "passive"))
      (node (ref "C16") (pin "2") (pinfunction "2_2") (pintype "passive"))
      (node (ref "C17") (pin "2") (pinfunction "2_2") (pintype "passive"))
      (node (ref "C18") (pin "2") (pinfunction "2_2") (pintype "passive"))
      (node (ref "C19") (pin "2") (pinfunction "2_2") (pintype "passive"))
      (node (ref "C20") (pin "2") (pinfunction "2_2") (pintype "passive"))
      (node (ref "C21") (pin "2") (pinfunction "2_2") (pintype "passive"))
      (node (ref "C22") (pin "2") (pinfunction "2_2") (pintype "passive"))
      (node (ref "C23") (pin "2") (pinfunction "2_2") (pintype "passive"))
      (node (ref "C24") (pin "2") (pinfunction "2_2") (pintype "passive"))
      (node (ref "C25") (pin "2") (pinfunction "2_2") (pintype "passive"))
      (node (ref "C26") (pin "2") (pinfunction "2_2") (pintype "passive"))
      (node (ref "FB2") (pin "2") (pinfunction "2_2") (pintype "passive"))
      (node (ref "FB3") (pin "2") (pinfunction "2_2") (pintype "passive"))
      (node (ref "P4") (pin "3") (pinfunction "3_3") (pintype "passive"))
      (node (ref "P4") (pin "4") (pinfunction "4_4") (pintype "passive"))
      (node (ref "R11") (pin "1") (pinfunction "1_1") (pintype "passive"))
      (node (ref "R12") (pin "1") (pinfunction "1_1") (pintype "passive"))
      (node (ref "R2") (pin "1") (pinfunction "1_1") (pintype "passive"))
      (node (ref "R4") (pin "2") (pinfunction "2_2") (pintype "passive"))
      (node (ref "R5") (pin "2") (pinfunction "2_2") (pintype "passive"))
      (node (ref "SWD/ISP") (pin "10") (pinfunction "10_10") (pintype "passive"))
      (node (ref "SWD/ISP") (pin "7") (pinfunction "7_7") (pintype "passive"))
      (node (ref "U1") (pin "108") (pinfunction "VDD_108") (pintype "passive"))
      (node (ref "U1") (pin "121") (pinfunction "VDD_121") (pintype "passive"))
      (node (ref "U1") (pin "131") (pinfunction "VDD_131") (pintype "passive"))
      (node (ref "U1") (pin "144") (pinfunction "VDD_144") (pintype "passive"))
      (node (ref "U1") (pin "17") (pinfunction "VDD_17") (pintype "passive"))
      (node (ref "U1") (pin "30") (pinfunction "VDD_30") (pintype "passive"))
      (node (ref "U1") (pin "39") (pinfunction "VDD_39") (pintype "passive"))
      (node (ref "U1") (pin "52") (pinfunction "VDD_52") (pintype "passive"))
      (node (ref "U1") (pin "6") (pinfunction "VBAT_6") (pintype "passive"))
      (node (ref "U1") (pin "62") (pinfunction "VDD_62") (pintype "passive"))
      (node (ref "U1") (pin "72") (pinfunction "VDD_72") (pintype "passive"))
      (node (ref "U1") (pin "84") (pinfunction "VDD_84") (pintype "passive"))
      (node (ref "U1") (pin "95") (pinfunction "VDD_95") (pintype "passive"))
      (node (ref "U2") (pin "5") (pinfunction "VOUT_5") (pintype "passive"))
    )
    (net (code "116") (name "5V") (class "Default")
      (node (ref "C11") (pin "2") (pinfunction "2_2") (pintype "passive"))
      (node (ref "C12") (pin "2") (pinfunction "2_2") (pintype "passive"))
      (node (ref "P4") (pin "5") (pinfunction "5_5") (pintype "passive"))
      (node (ref "P4") (pin "6") (pinfunction "6_6") (pintype "passive"))
      (node (ref "SWD/ISP") (pin "2") (pinfunction "2_2") (pintype "passive"))
      (node (ref "TYPE-C") (pin "A4B9") (pinfunction "VBUS_A4B9") (pintype "passive"))
      (node (ref "TYPE-C") (pin "B4A9") (pinfunction "VBUS_B4A9") (pintype "passive"))
      (node (ref "U2") (pin "1") (pinfunction "VIN_1") (pintype "passive"))
      (node (ref "U2") (pin "3") (pinfunction "EN_3") (pintype "passive"))
    )
    (net (code "117") (name "GND") (class "Default")
      (node (ref "3V3") (pin "2") (pinfunction "2_2") (pintype "passive"))
      (node (ref "C1") (pin "2") (pinfunction "2_2") (pintype "passive"))
      (node (ref "C10") (pin "2") (pinfunction "2_2") (pintype "passive"))
      (node (ref "C11") (pin "1") (pinfunction "1_1") (pintype "passive"))
      (node (ref "C12") (pin "1") (pinfunction "1_1") (pintype "passive"))
      (node (ref "C13") (pin "1") (pinfunction "1_1") (pintype "passive"))
      (node (ref "C14") (pin "1") (pinfunction "1_1") (pintype "passive"))
      (node (ref "C15") (pin "1") (pinfunction "1_1") (pintype "passive"))
      (node (ref "C16") (pin "1") (pinfunction "1_1") (pintype "passive"))
      (node (ref "C17") (pin "1") (pinfunction "1_1") (pintype "passive"))
      (node (ref "C18") (pin "1") (pinfunction "1_1") (pintype "passive"))
      (node (ref "C19") (pin "1") (pinfunction "1_1") (pintype "passive"))
      (node (ref "C2") (pin "1") (pinfunction "1_1") (pintype "passive"))
      (node (ref "C20") (pin "1") (pinfunction "1_1") (pintype "passive"))
      (node (ref "C21") (pin "1") (pinfunction "1_1") (pintype "passive"))
      (node (ref "C22") (pin "1") (pinfunction "1_1") (pintype "passive"))
      (node (ref "C23") (pin "1") (pinfunction "1_1") (pintype "passive"))
      (node (ref "C24") (pin "1") (pinfunction "1_1") (pintype "passive"))
      (node (ref "C25") (pin "1") (pinfunction "1_1") (pintype "passive"))
      (node (ref "C26") (pin "1") (pinfunction "1_1") (pintype "passive"))
      (node (ref "C3") (pin "1") (pinfunction "1_1") (pintype "passive"))
      (node (ref "C4") (pin "1") (pinfunction "1_1") (pintype "passive"))
      (node (ref "C5") (pin "1") (pinfunction "1_1") (pintype "passive"))
      (node (ref "C6") (pin "2") (pinfunction "2_2") (pintype "passive"))
      (node (ref "C7") (pin "2") (pinfunction "2_2") (pintype "passive"))
      (node (ref "C8") (pin "1") (pinfunction "1_1") (pintype "passive"))
      (node (ref "C9") (pin "1") (pinfunction "1_1") (pintype "passive"))
      (node (ref "P4") (pin "1") (pinfunction "1_1") (pintype "passive"))
      (node (ref "P4") (pin "2") (pinfunction "2_2") (pintype "passive"))
      (node (ref "R10") (pin "1") (pinfunction "1_1") (pintype "passive"))
      (node (ref "R3") (pin "2") (pinfunction "2_2") (pintype "passive"))
      (node (ref "R8") (pin "1") (pinfunction "1_1") (pintype "passive"))
      (node (ref "R9") (pin "1") (pinfunction "1_1") (pintype "passive"))
      (node (ref "RESET") (pin "3") (pinfunction "3_3") (pintype "passive"))
      (node (ref "RESET") (pin "4") (pinfunction "4_4") (pintype "passive"))
      (node (ref "SWD/ISP") (pin "1") (pinfunction "1_1") (pintype "passive"))
      (node (ref "SWD/ISP") (pin "4") (pinfunction "4_4") (pintype "passive"))
      (node (ref "TYPE-C") (pin "1") (pinfunction "SHELL_1") (pintype "passive"))
      (node (ref "TYPE-C") (pin "2") (pinfunction "SHELL_2") (pintype "passive"))
      (node (ref "TYPE-C") (pin "3") (pinfunction "SHELL_3") (pintype "passive"))
      (node (ref "TYPE-C") (pin "4") (pinfunction "SHELL_4") (pintype "passive"))
      (node (ref "TYPE-C") (pin "A1B12") (pinfunction "GND_A1B12") (pintype "passive"))
      (node (ref "TYPE-C") (pin "B1A12") (pinfunction "GND_B1A12") (pintype "passive"))
      (node (ref "U1") (pin "107") (pinfunction "VSS_107") (pintype "passive"))
      (node (ref "U1") (pin "120") (pinfunction "VSS_120") (pintype "passive"))
      (node (ref "U1") (pin "130") (pinfunction "VSS_130") (pintype "passive"))
      (node (ref "U1") (pin "16") (pinfunction "VSS_16") (pintype "passive"))
      (node (ref "U1") (pin "31") (pinfunction "VSSA_31") (pintype "passive"))
      (node (ref "U1") (pin "38") (pinfunction "VSS_38") (pintype "passive"))
      (node (ref "U1") (pin "51") (pinfunction "VSS_51") (pintype "passive"))
      (node (ref "U1") (pin "61") (pinfunction "VSS_61") (pintype "passive"))
      (node (ref "U1") (pin "83") (pinfunction "VSS_83") (pintype "passive"))
      (node (ref "U1") (pin "94") (pinfunction "VSS_94") (pintype "passive"))
      (node (ref "U2") (pin "2") (pinfunction "GND_2") (pintype "passive"))
      (node (ref "X1") (pin "2") (pinfunction "GND_2") (pintype "passive"))
      (node (ref "X1") (pin "4") (pinfunction "GND_4") (pintype "passive"))
    )
    (net (code "118") (name "Net-(3V3-Pad1)") (class "Default")
      (node (ref "3V3") (pin "1") (pinfunction "1_1") (pintype "passive"))
      (node (ref "R4") (pin "1") (pinfunction "1_1") (pintype "passive"))
    )
    (net (code "119") (name "Net-(F9-Pad1)") (class "Default")
      (node (ref "F9") (pin "1") (pinfunction "1_1") (pintype "passive"))
      (node (ref "R11") (pin "2") (pinfunction "2_2") (pintype "passive"))
    )
    (net (code "120") (name "Net-(F10-Pad1)") (class "Default")
      (node (ref "F10") (pin "1") (pinfunction "1_1") (pintype "passive"))
      (node (ref "R12") (pin "2") (pinfunction "2_2") (pintype "passive"))
    )
    (net (code "121") (name "Net-(TYPE-C-CC1)") (class "Default")
      (node (ref "R9") (pin "2") (pinfunction "2_2") (pintype "passive"))
      (node (ref "TYPE-C") (pin "A5") (pinfunction "CC1_A5") (pintype "passive"))
    )
    (net (code "122") (name "Net-(TYPE-C-CC2)") (class "Default")
      (node (ref "R8") (pin "2") (pinfunction "2_2") (pintype "passive"))
      (node (ref "TYPE-C") (pin "B5") (pinfunction "CC2_B5") (pintype "passive"))
    )
    (net (code "123") (name "Net-(TYPE-C-DN1)") (class "Default")
      (node (ref "R7") (pin "2") (pinfunction "2_2") (pintype "passive"))
      (node (ref "TYPE-C") (pin "A7") (pinfunction "DN1_A7") (pintype "passive"))
      (node (ref "TYPE-C") (pin "B7") (pinfunction "DN2_B7") (pintype "passive"))
    )
    (net (code "124") (name "Net-(TYPE-C-DP1)") (class "Default")
      (node (ref "R5") (pin "1") (pinfunction "1_1") (pintype "passive"))
      (node (ref "R6") (pin "2") (pinfunction "2_2") (pintype "passive"))
      (node (ref "TYPE-C") (pin "A6") (pinfunction "DP1_A6") (pintype "passive"))
      (node (ref "TYPE-C") (pin "B6") (pinfunction "DP2_B6") (pintype "passive"))
    )
    (net (code "125") (name "Net-(U1-PDR_ON)") (class "Default")
      (node (ref "FB3") (pin "1") (pinfunction "1_1") (pintype "passive"))
      (node (ref "R3") (pin "1") (pinfunction "1_1") (pintype "passive"))
      (node (ref "U1") (pin "143") (pinfunction "PDR_ON_143") (pintype "passive"))
    )
    (net (code "126") (name "Net-(U1-PH0-OSC_IN)") (class "Default")
      (node (ref "C2") (pin "2") (pinfunction "2_2") (pintype "passive"))
      (node (ref "R1") (pin "2") (pinfunction "2_2") (pintype "passive"))
      (node (ref "U1") (pin "23") (pinfunction "PH0-OSC_IN_23") (pintype "passive"))
      (node (ref "X1") (pin "3") (pinfunction "OSC2_3") (pintype "passive"))
    )
    (net (code "127") (name "Net-(U1-PH1-OSC_OUT)") (class "Default")
      (node (ref "C1") (pin "1") (pinfunction "1_1") (pintype "passive"))
      (node (ref "R1") (pin "1") (pinfunction "1_1") (pintype "passive"))
      (node (ref "U1") (pin "24") (pinfunction "PH1-OSC_OUT_24") (pintype "passive"))
      (node (ref "X1") (pin "1") (pinfunction "OSC1_1") (pintype "passive"))
    )
    (net (code "128") (name "Net-(U1-Vcap_1)") (class "Default")
      (node (ref "C6") (pin "1") (pinfunction "1_1") (pintype "passive"))
      (node (ref "U1") (pin "71") (pinfunction "Vcap_1_71") (pintype "passive"))
    )
    (net (code "129") (name "Net-(U1-Vcap_2)") (class "Default")
      (node (ref "C7") (pin "1") (pinfunction "1_1") (pintype "passive"))
      (node (ref "U1") (pin "106") (pinfunction "Vcap_2_106") (pintype "passive"))
    )
    (net (code "130") (name "Net-(U1-Vref+)") (class "Default")
      (node (ref "C5") (pin "2") (pinfunction "2_2") (pintype "passive"))
      (node (ref "FB1") (pin "1") (pinfunction "1_1") (pintype "passive"))
      (node (ref "U1") (pin "32") (pinfunction "Vref+_32") (pintype "passive"))
    )
    (net (code "131") (name "VDDA") (class "Default")
      (node (ref "C8") (pin "2") (pinfunction "2_2") (pintype "passive"))
      (node (ref "C9") (pin "2") (pinfunction "2_2") (pintype "passive"))
      (node (ref "FB1") (pin "2") (pinfunction "2_2") (pintype "passive"))
      (node (ref "FB2") (pin "1") (pinfunction "1_1") (pintype "passive"))
      (node (ref "U1") (pin "33") (pinfunction "VDDA_33") (pintype "passive"))
    )
    (net (code "132") (name "unconnected-(TYPE-C-SBU1-PadA8)") (class "Default")
      (node (ref "TYPE-C") (pin "A8") (pinfunction "SBU1_A8") (pintype "passive+no_connect"))
    )
    (net (code "133") (name "unconnected-(TYPE-C-SBU2-PadB8)") (class "Default")
      (node (ref "TYPE-C") (pin "B8") (pinfunction "SBU2_B8") (pintype "passive+no_connect"))
    )
    (net (code "134") (name "unconnected-(U2-NC-Pad4)") (class "Default")
      (node (ref "U2") (pin "4") (pinfunction "NC_4") (pintype "passive+no_connect"))
    )
  )
)
